# HM_EX_DS18B20.net
KiCad netlist of a schematic drawn in EAGLE
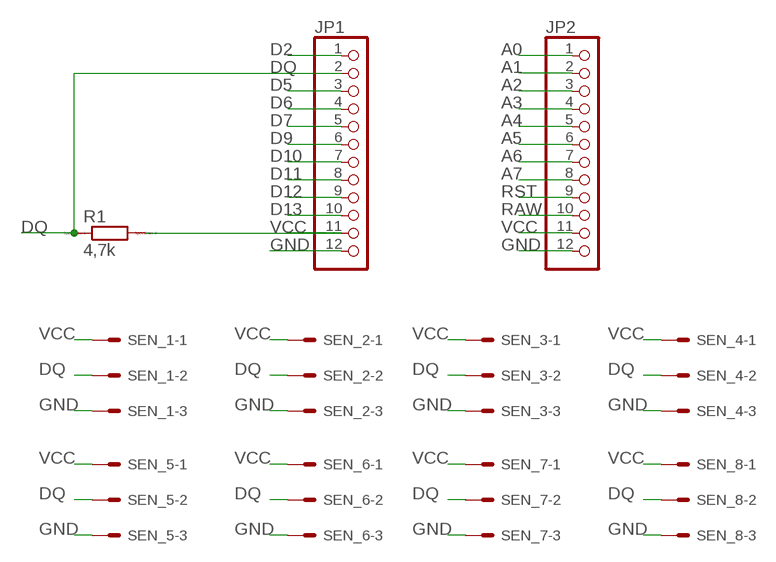
[diagram p0: schematic, sheet 1]

(export (version "E")
  (design (tool "Eeschema 10.0.6"))
  (components
    (comp (ref "JP1")
      (value "PINHD-1X12")
      (footprint "eagle-import:1X12")
      (libsource (lib "eagle-import") (part "PINHD-1X12"))
    )
    (comp (ref "JP2")
      (value "PINHD-1X12")
      (footprint "eagle-import:1X12")
      (libsource (lib "eagle-import") (part "PINHD-1X12"))
    )
    (comp (ref "R1")
      (value "4,7k")
      (footprint "eagle-import:0207_10")
      (libsource (lib "eagle-import") (part "R0207/10"))
    )
    (comp (ref "SEN_1")
      (value "22-27-2031-03")
      (footprint "eagle-import:6410-03")
      (fields (field (name "MF") "MOLEX"))
      (libsource (lib "eagle-import") (part "22-?-0327-2031"))
    )
    (comp (ref "SEN_2")
      (value "22-27-2031-03")
      (footprint "eagle-import:6410-03")
      (fields (field (name "MF") "MOLEX"))
      (libsource (lib "eagle-import") (part "22-?-0327-2031"))
    )
    (comp (ref "SEN_3")
      (value "22-27-2031-03")
      (footprint "eagle-import:6410-03")
      (fields (field (name "MF") "MOLEX"))
      (libsource (lib "eagle-import") (part "22-?-0327-2031"))
    )
    (comp (ref "SEN_4")
      (value "22-27-2031-03")
      (footprint "eagle-import:6410-03")
      (fields (field (name "MF") "MOLEX"))
      (libsource (lib "eagle-import") (part "22-?-0327-2031"))
    )
    (comp (ref "SEN_5")
      (value "22-27-2031-03")
      (footprint "eagle-import:6410-03")
      (fields (field (name "MF") "MOLEX"))
      (libsource (lib "eagle-import") (part "22-?-0327-2031"))
    )
    (comp (ref "SEN_6")
      (value "22-27-2031-03")
      (footprint "eagle-import:6410-03")
      (fields (field (name "MF") "MOLEX"))
      (libsource (lib "eagle-import") (part "22-?-0327-2031"))
    )
    (comp (ref "SEN_7")
      (value "22-27-2031-03")
      (footprint "eagle-import:6410-03")
      (fields (field (name "MF") "MOLEX"))
      (libsource (lib "eagle-import") (part "22-?-0327-2031"))
    )
    (comp (ref "SEN_8")
      (value "22-27-2031-03")
      (footprint "eagle-import:6410-03")
      (fields (field (name "MF") "MOLEX"))
      (libsource (lib "eagle-import") (part "22-?-0327-2031"))
    )
  )
  (nets
    (net (code "1") (name "/A0") (class "Default")
      (node (ref "JP2") (pin "1") (pinfunction "1_1") (pintype "passive"))
    )
    (net (code "2") (name "/A1") (class "Default")
      (node (ref "JP2") (pin "2") (pinfunction "2_2") (pintype "passive"))
    )
    (net (code "3") (name "/A2") (class "Default")
      (node (ref "JP2") (pin "3") (pinfunction "3_3") (pintype "passive"))
    )
    (net (code "4") (name "/A3") (class "Default")
      (node (ref "JP2") (pin "4") (pinfunction "4_4") (pintype "passive"))
    )
    (net (code "5") (name "/A4") (class "Default")
      (node (ref "JP2") (pin "5") (pinfunction "5_5") (pintype "passive"))
    )
    (net (code "6") (name "/A5") (class "Default")
      (node (ref "JP2") (pin "6") (pinfunction "6_6") (pintype "passive"))
    )
    (net (code "7") (name "/A6") (class "Default")
      (node (ref "JP2") (pin "7") (pinfunction "7_7") (pintype "passive"))
    )
    (net (code "8") (name "/A7") (class "Default")
      (node (ref "JP2") (pin "8") (pinfunction "8_8") (pintype "passive"))
    )
    (net (code "9") (name "/D2") (class "Default")
      (node (ref "JP1") (pin "1") (pinfunction "1_1") (pintype "passive"))
    )
    (net (code "10") (name "/D5") (class "Default")
      (node (ref "JP1") (pin "3") (pinfunction "3_3") (pintype "passive"))
    )
    (net (code "11") (name "/D6") (class "Default")
      (node (ref "JP1") (pin "4") (pinfunction "4_4") (pintype "passive"))
    )
    (net (code "12") (name "/D7") (class "Default")
      (node (ref "JP1") (pin "5") (pinfunction "5_5") (pintype "passive"))
    )
    (net (code "13") (name "/D9") (class "Default")
      (node (ref "JP1") (pin "6") (pinfunction "6_6") (pintype "passive"))
    )
    (net (code "14") (name "/D10") (class "Default")
      (node (ref "JP1") (pin "7") (pinfunction "7_7") (pintype "passive"))
    )
    (net (code "15") (name "/D11") (class "Default")
      (node (ref "JP1") (pin "8") (pinfunction "8_8") (pintype "passive"))
    )
    (net (code "16") (name "/D12") (class "Default")
      (node (ref "JP1") (pin "9") (pinfunction "9_9") (pintype "passive"))
    )
    (net (code "17") (name "/D13") (class "Default")
      (node (ref "JP1") (pin "10") (pinfunction "10_10") (pintype "passive"))
    )
    (net (code "18") (name "/DQ") (class "Default")
      (node (ref "JP1") (pin "2") (pinfunction "2_2") (pintype "passive"))
      (node (ref "R1") (pin "1") (pinfunction "1_1") (pintype "passive"))
      (node (ref "SEN_1") (pin "2") (pinfunction "S_2") (pintype "passive"))
      (node (ref "SEN_2") (pin "2") (pinfunction "S_2") (pintype "passive"))
      (node (ref "SEN_3") (pin "2") (pinfunction "S_2") (pintype "passive"))
      (node (ref "SEN_4") (pin "2") (pinfunction "S_2") (pintype "passive"))
      (node (ref "SEN_5") (pin "2") (pinfunction "S_2") (pintype "passive"))
      (node (ref "SEN_6") (pin "2") (pinfunction "S_2") (pintype "passive"))
      (node (ref "SEN_7") (pin "2") (pinfunction "S_2") (pintype "passive"))
      (node (ref "SEN_8") (pin "2") (pinfunction "S_2") (pintype "passive"))
    )
    (net (code "19") (name "/GND") (class "Default")
      (node (ref "JP1") (pin "12") (pinfunction "12_12") (pintype "passive"))
      (node (ref "JP2") (pin "12") (pinfunction "12_12") (pintype "passive"))
      (node (ref "SEN_1") (pin "3") (pinfunction "S_3") (pintype "passive"))
      (node (ref "SEN_2") (pin "3") (pinfunction "S_3") (pintype "passive"))
      (node (ref "SEN_3") (pin "3") (pinfunction "S_3") (pintype "passive"))
      (node (ref "SEN_4") (pin "3") (pinfunction "S_3") (pintype "passive"))
      (node (ref "SEN_5") (pin "3") (pinfunction "S_3") (pintype "passive"))
      (node (ref "SEN_6") (pin "3") (pinfunction "S_3") (pintype "passive"))
      (node (ref "SEN_7") (pin "3") (pinfunction "S_3") (pintype "passive"))
      (node (ref "SEN_8") (pin "3") (pinfunction "S_3") (pintype "passive"))
    )
    (net (code "20") (name "/RAW") (class "Default")
      (node (ref "JP2") (pin "10") (pinfunction "10_10") (pintype "passive"))
    )
    (net (code "21") (name "/RST") (class "Default")
      (node (ref "JP2") (pin "9") (pinfunction "9_9") (pintype "passive"))
    )
    (net (code "22") (name "/VCC") (class "Default")
      (node (ref "JP1") (pin "11") (pinfunction "11_11") (pintype "passive"))
      (node (ref "JP2") (pin "11") (pinfunction "11_11") (pintype "passive"))
      (node (ref "R1") (pin "2") (pinfunction "2_2") (pintype "passive"))
      (node (ref "SEN_1") (pin "1") (pinfunction "S_1") (pintype "passive"))
      (node (ref "SEN_2") (pin "1") (pinfunction "S_1") (pintype "passive"))
      (node (ref "SEN_3") (pin "1") (pinfunction "S_1") (pintype "passive"))
      (node (ref "SEN_4") (pin "1") (pinfunction "S_1") (pintype "passive"))
      (node (ref "SEN_5") (pin "1") (pinfunction "S_1") (pintype "passive"))
      (node (ref "SEN_6") (pin "1") (pinfunction "S_1") (pintype "passive"))
      (node (ref "SEN_7") (pin "1") (pinfunction "S_1") (pintype "passive"))
      (node (ref "SEN_8") (pin "1") (pinfunction "S_1") (pintype "passive"))
    )
  )
)
